# 3V3_Regulator.net
KiCad netlist of a schematic drawn in Altium Designer
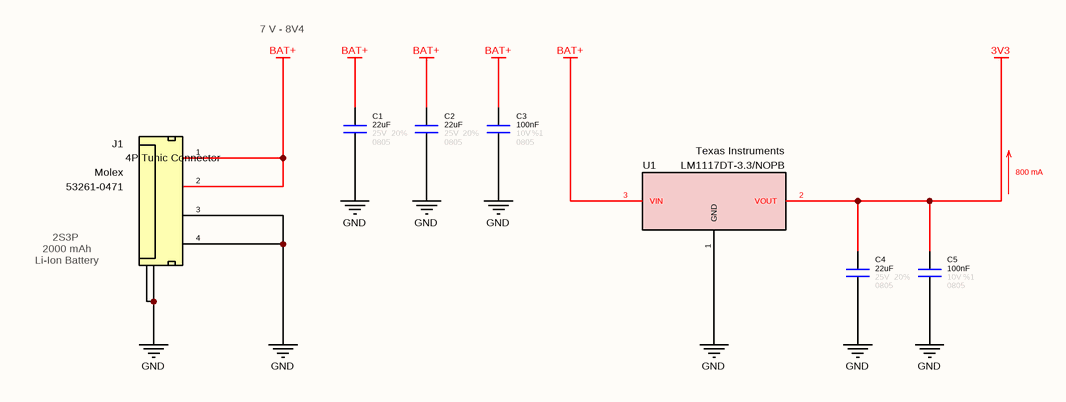
[diagram p0: 3V3 Regulator.SchDoc]

(export (version "E")
  (design (tool "Eeschema 10.0.6"))
  (components
    (comp (ref "C1")
      (value "22uF")
      (footprint "CAPACITOR_0805")
      (description "Multilayer Ceramic Capacitors MLCC - SMD/SMT 22UF 25V 10% 1210")
      (fields
        (field (name "MANUFACTURER PART NUMBER") "GRM21BR61E226ME44L")
        (field (name "TOLERANCE") "20%")
        (field (name "CASE") "0805")
        (field (name "VOLTAGE") "25V")
        (field (name "Comment") "Capacitor - 22uF [1210] (Ceramic)")
      )
      (libsource (lib "Akkoyun") (part "Capacitor - 22uF [0805-25V]"))
    )
    (comp (ref "C2")
      (value "22uF")
      (footprint "CAPACITOR_0805")
      (description "Multilayer Ceramic Capacitors MLCC - SMD/SMT 22UF 25V 10% 1210")
      (fields
        (field (name "MANUFACTURER PART NUMBER") "GRM21BR61E226ME44L")
        (field (name "TOLERANCE") "20%")
        (field (name "CASE") "0805")
        (field (name "VOLTAGE") "25V")
        (field (name "Comment") "Capacitor - 22uF [1210] (Ceramic)")
      )
      (libsource (lib "Akkoyun") (part "Capacitor - 22uF [0805-25V]"))
    )
    (comp (ref "C3")
      (value "100nF")
      (footprint "CAPACITOR_0805")
      (description "Capacitor (MLCC) - 100nF / 10V / 0805")
      (fields
        (field (name "MANUFACTURER PART NUMBER") "C0805C104K8JACAUTO")
        (field (name "TOLERANCE") "%1")
        (field (name "VOLTAGE") "10V")
        (field (name "CASE") "0805")
        (field (name "Comment") "Capacitor - 100nF [0805] (MLCC)")
      )
      (libsource (lib "Akkoyun") (part "Capacitor - 100nF [0805-10V]"))
    )
    (comp (ref "C4")
      (value "22uF")
      (footprint "CAPACITOR_0805")
      (description "Multilayer Ceramic Capacitors MLCC - SMD/SMT 22UF 25V 10% 1210")
      (fields
        (field (name "MANUFACTURER PART NUMBER") "GRM21BR61E226ME44L")
        (field (name "TOLERANCE") "20%")
        (field (name "CASE") "0805")
        (field (name "VOLTAGE") "25V")
        (field (name "Comment") "Capacitor - 22uF [1210] (Ceramic)")
      )
      (libsource (lib "Akkoyun") (part "Capacitor - 22uF [0805-25V]"))
    )
    (comp (ref "C5")
      (value "100nF")
      (footprint "CAPACITOR_0805")
      (description "Capacitor (MLCC) - 100nF / 10V / 0805")
      (fields
        (field (name "MANUFACTURER PART NUMBER") "C0805C104K8JACAUTO")
        (field (name "TOLERANCE") "%1")
        (field (name "VOLTAGE") "10V")
        (field (name "CASE") "0805")
        (field (name "Comment") "Capacitor - 100nF [0805] (MLCC)")
      )
      (libsource (lib "Akkoyun") (part "Capacitor - 100nF [0805-10V]"))
    )
    (comp (ref "J1")
      (value "4P SMD Tunic Connector")
      (footprint "Connector_Tunic 4P")
      (description "Mini Tunic Connector with 4P")
      (fields
        (field (name "MANUFACTURER NAME") "Molex")
        (field (name "MANUFACTURER PART NUMBER") "53261-0471")
      )
      (libsource (lib "Akkoyun") (part "Connector - Mini Tunic 4P (1.25)"))
    )
    (comp (ref "U1")
      (value "LDO Regulator")
      (footprint "TO-252")
      (description "LDO Voltage Regulators 800MA LDO LINEAR REG")
      (fields
        (field (name "MANUFACTURER PART NUMBER") "LM1117DT-3.3/NOPB")
        (field (name "MANUFACTURER NAME") "Texas Instruments")
      )
      (libsource (lib "Akkoyun") (part "IC - LM1117DT-3.3/NOPB"))
    )
  )
  (nets
    (net (code "1") (name "3V3") (class "Default")
      (node (ref "C4") (pin "2") (pinfunction "2_2") (pintype "passive"))
      (node (ref "C5") (pin "2") (pinfunction "2_2") (pintype "passive"))
      (node (ref "U1") (pin "2") (pinfunction "VOUT_2") (pintype "power_in"))
    )
    (net (code "2") (name "BAT+") (class "Default")
      (node (ref "C1") (pin "2") (pinfunction "2_2") (pintype "passive"))
      (node (ref "C2") (pin "2") (pinfunction "2_2") (pintype "passive"))
      (node (ref "C3") (pin "2") (pinfunction "2_2") (pintype "passive"))
      (node (ref "J1") (pin "1") (pinfunction "BAT+_1") (pintype "passive"))
      (node (ref "J1") (pin "2") (pinfunction "BAT+_2") (pintype "passive"))
      (node (ref "U1") (pin "3") (pinfunction "VIN_3") (pintype "power_in"))
    )
    (net (code "3") (name "GND") (class "Default")
      (node (ref "C1") (pin "1") (pinfunction "1_1") (pintype "passive"))
      (node (ref "C2") (pin "1") (pinfunction "1_1") (pintype "passive"))
      (node (ref "C3") (pin "1") (pinfunction "1_1") (pintype "passive"))
      (node (ref "C4") (pin "1") (pinfunction "1_1") (pintype "passive"))
      (node (ref "C5") (pin "1") (pinfunction "1_1") (pintype "passive"))
      (node (ref "J1") (pin "3") (pinfunction "BAT-_3") (pintype "passive"))
      (node (ref "J1") (pin "4") (pinfunction "BAT-_4") (pintype "passive"))
      (node (ref "J1") (pin "5") (pinfunction "GND_5") (pintype "passive"))
      (node (ref "J1") (pin "6") (pinfunction "GND_6") (pintype "passive"))
      (node (ref "U1") (pin "1") (pinfunction "GND_1") (pintype "power_in"))
    )
  )
)
